# CFA_s.net
KiCad netlist of a schematic drawn in EAGLE
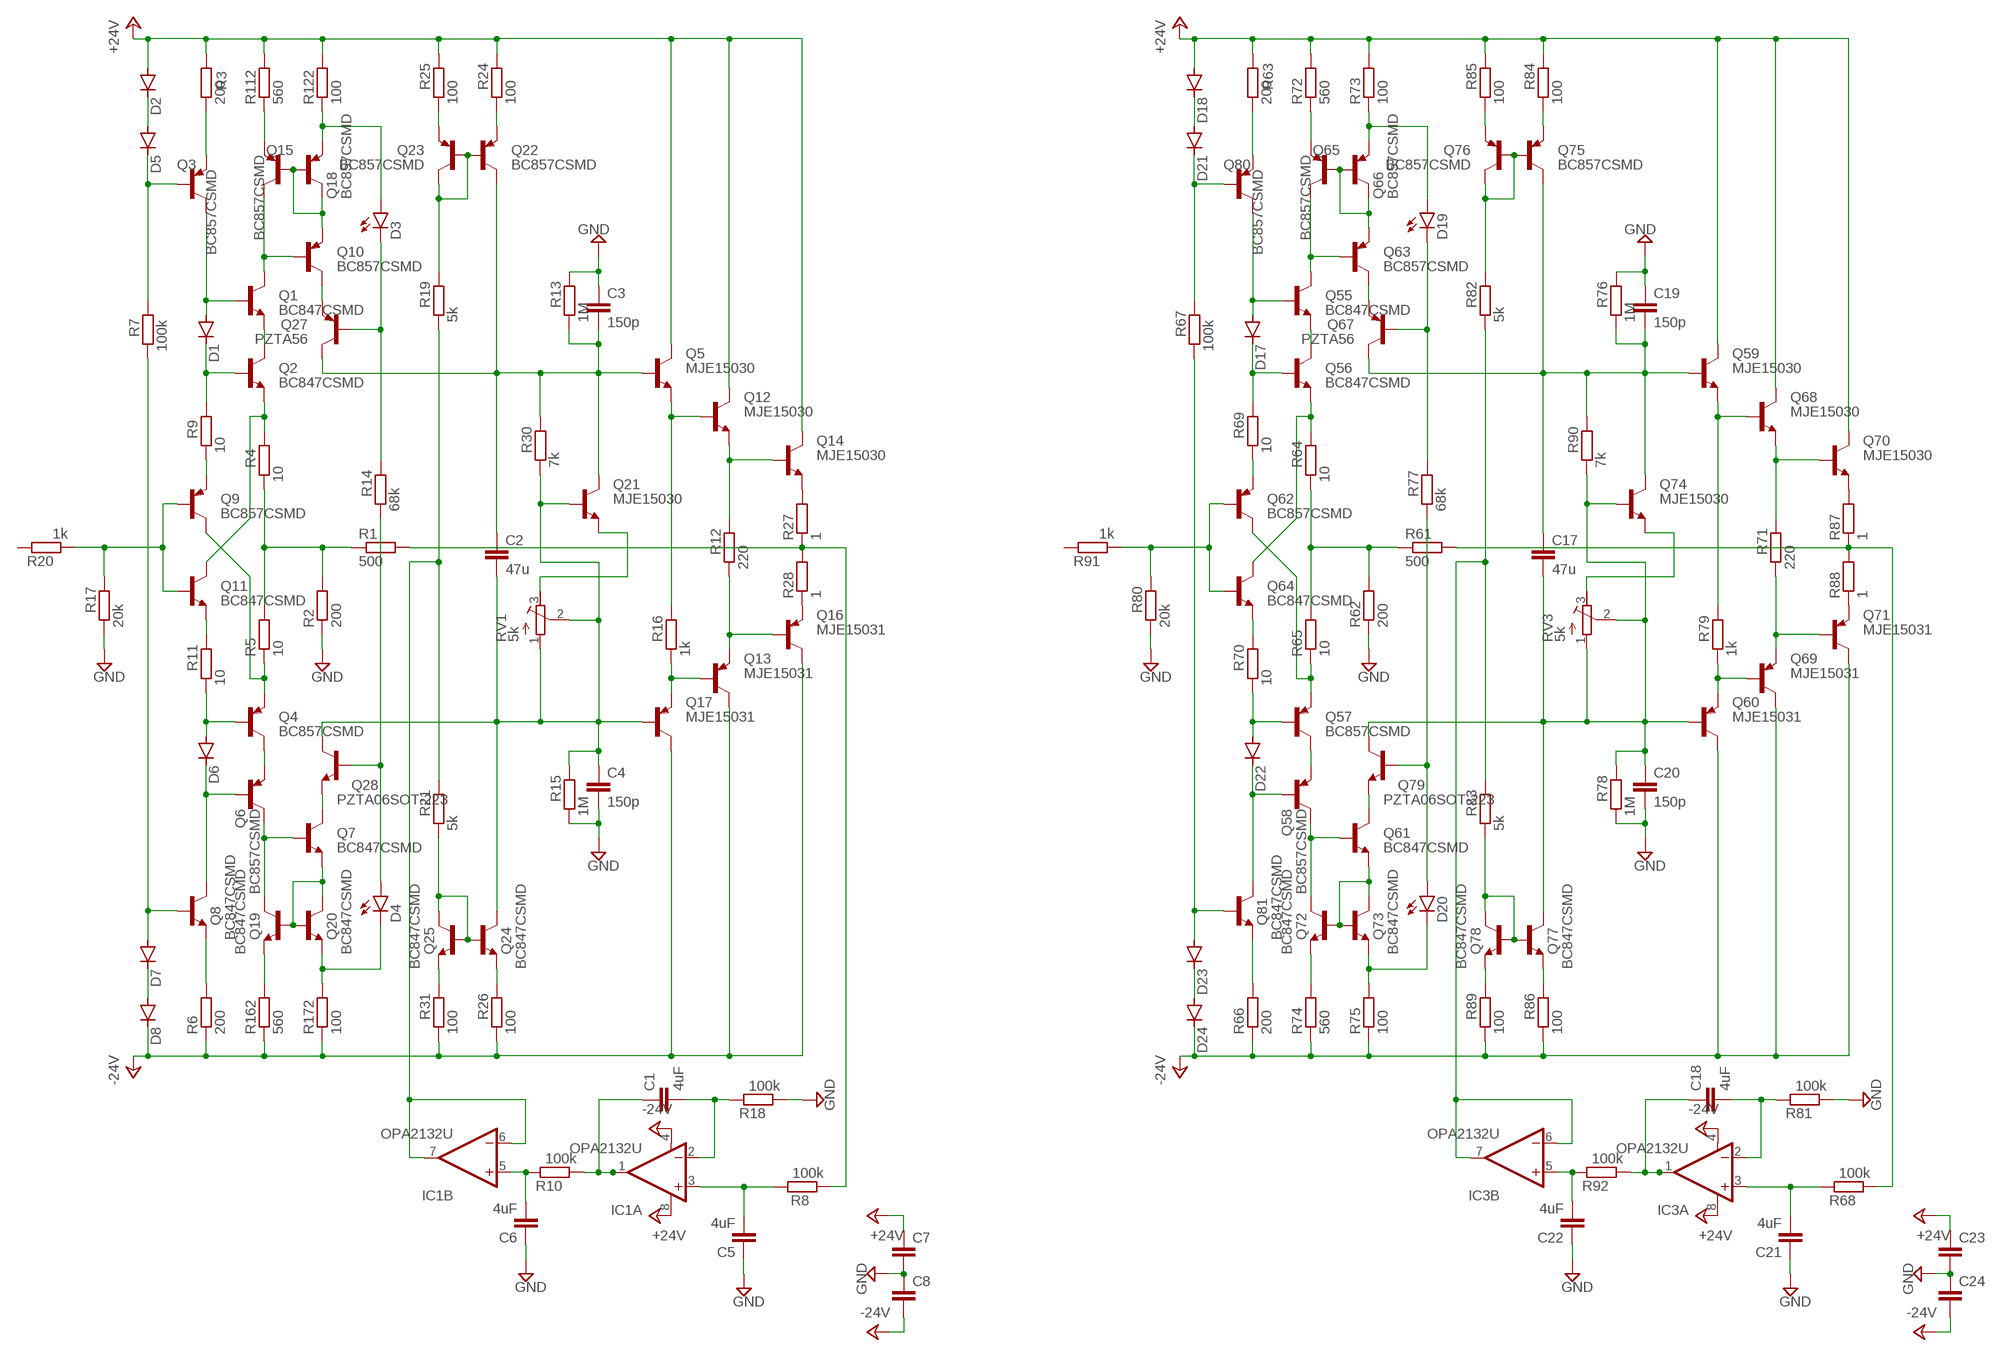
[diagram p0: schematic, sheet 1]

(export (version "E")
  (design (tool "Eeschema 10.0.6"))
  (components
    (comp (ref "C1")
      (value "4uF")
      (footprint "eagle-import:C1210")
      (fields (field (name "SPICEPREFIX") "C"))
      (libsource (lib "eagle-import") (part "C-EUC1210"))
    )
    (comp (ref "C2")
      (value "47u")
      (footprint "eagle-import:C1210")
      (fields (field (name "SPICEPREFIX") "C"))
      (libsource (lib "eagle-import") (part "C-EUC1210"))
    )
    (comp (ref "C3")
      (value "150p")
      (footprint "eagle-import:C0805")
      (fields (field (name "SPICEPREFIX") "C"))
      (libsource (lib "eagle-import") (part "C-EUC0805"))
    )
    (comp (ref "C4")
      (value "150p")
      (footprint "eagle-import:C0805")
      (fields (field (name "SPICEPREFIX") "C"))
      (libsource (lib "eagle-import") (part "C-EUC0805"))
    )
    (comp (ref "C5")
      (value "4uF")
      (footprint "eagle-import:C1210")
      (fields (field (name "SPICEPREFIX") "C"))
      (libsource (lib "eagle-import") (part "C-EUC1210"))
    )
    (comp (ref "C6")
      (value "4uF")
      (footprint "eagle-import:C1210")
      (fields (field (name "SPICEPREFIX") "C"))
      (libsource (lib "eagle-import") (part "C-EUC1210"))
    )
    (comp (ref "C7")
      (value "C-EUC0603K")
      (footprint "eagle-import:C0603K")
      (libsource (lib "eagle-import") (part "C-EUC0603K"))
    )
    (comp (ref "C8")
      (value "C-EUC0603K")
      (footprint "eagle-import:C0603K")
      (libsource (lib "eagle-import") (part "C-EUC0603K"))
    )
    (comp (ref "C17")
      (value "47u")
      (footprint "eagle-import:C1210")
      (fields (field (name "SPICEPREFIX") "C"))
      (libsource (lib "eagle-import") (part "C-EUC1210"))
    )
    (comp (ref "C18")
      (value "4uF")
      (footprint "eagle-import:C1210")
      (fields (field (name "SPICEPREFIX") "C"))
      (libsource (lib "eagle-import") (part "C-EUC1210"))
    )
    (comp (ref "C19")
      (value "150p")
      (footprint "eagle-import:C0805")
      (fields (field (name "SPICEPREFIX") "C"))
      (libsource (lib "eagle-import") (part "C-EUC0805"))
    )
    (comp (ref "C20")
      (value "150p")
      (footprint "eagle-import:C0805")
      (fields (field (name "SPICEPREFIX") "C"))
      (libsource (lib "eagle-import") (part "C-EUC0805"))
    )
    (comp (ref "C21")
      (value "4uF")
      (footprint "eagle-import:C1210")
      (fields (field (name "SPICEPREFIX") "C"))
      (libsource (lib "eagle-import") (part "C-EUC1210"))
    )
    (comp (ref "C22")
      (value "4uF")
      (footprint "eagle-import:C1210")
      (fields (field (name "SPICEPREFIX") "C"))
      (libsource (lib "eagle-import") (part "C-EUC1210"))
    )
    (comp (ref "C23")
      (value "C-EUC0603K")
      (footprint "eagle-import:C0603K")
      (libsource (lib "eagle-import") (part "C-EUC0603K"))
    )
    (comp (ref "C24")
      (value "C-EUC0603K")
      (footprint "eagle-import:C0603K")
      (libsource (lib "eagle-import") (part "C-EUC0603K"))
    )
    (comp (ref "D1")
      (value "DIODE-SOD80C")
      (footprint "eagle-import:SOD80C")
      (fields (field (name "SPICEPREFIX") "D"))
      (libsource (lib "eagle-import") (part "DIODE-SOD80C"))
    )
    (comp (ref "D2")
      (value "DIODE-SOD80C")
      (footprint "eagle-import:SOD80C")
      (fields (field (name "SPICEPREFIX") "D"))
      (libsource (lib "eagle-import") (part "DIODE-SOD80C"))
    )
    (comp (ref "D3")
      (value "LEDCHIPLED_1206")
      (footprint "eagle-import:CHIPLED_1206")
      (fields (field (name "SPICEPREFIX") "D"))
      (libsource (lib "eagle-import") (part "LEDCHIPLED_1206"))
    )
    (comp (ref "D4")
      (value "LEDCHIPLED_1206")
      (footprint "eagle-import:CHIPLED_1206")
      (fields (field (name "SPICEPREFIX") "D"))
      (libsource (lib "eagle-import") (part "LEDCHIPLED_1206"))
    )
    (comp (ref "D5")
      (value "DIODE-SOD80C")
      (footprint "eagle-import:SOD80C")
      (fields (field (name "SPICEPREFIX") "D"))
      (libsource (lib "eagle-import") (part "DIODE-SOD80C"))
    )
    (comp (ref "D6")
      (value "DIODE-SOD80C")
      (footprint "eagle-import:SOD80C")
      (fields (field (name "SPICEPREFIX") "D"))
      (libsource (lib "eagle-import") (part "DIODE-SOD80C"))
    )
    (comp (ref "D7")
      (value "DIODE-SOD80C")
      (footprint "eagle-import:SOD80C")
      (fields (field (name "SPICEPREFIX") "D"))
      (libsource (lib "eagle-import") (part "DIODE-SOD80C"))
    )
    (comp (ref "D8")
      (value "DIODE-SOD80C")
      (footprint "eagle-import:SOD80C")
      (fields (field (name "SPICEPREFIX") "D"))
      (libsource (lib "eagle-import") (part "DIODE-SOD80C"))
    )
    (comp (ref "D17")
      (value "DIODE-SOD80C")
      (footprint "eagle-import:SOD80C")
      (fields (field (name "SPICEPREFIX") "D"))
      (libsource (lib "eagle-import") (part "DIODE-SOD80C"))
    )
    (comp (ref "D18")
      (value "DIODE-SOD80C")
      (footprint "eagle-import:SOD80C")
      (fields (field (name "SPICEPREFIX") "D"))
      (libsource (lib "eagle-import") (part "DIODE-SOD80C"))
    )
    (comp (ref "D19")
      (value "LEDCHIPLED_1206")
      (footprint "eagle-import:CHIPLED_1206")
      (fields (field (name "SPICEPREFIX") "D"))
      (libsource (lib "eagle-import") (part "LEDCHIPLED_1206"))
    )
    (comp (ref "D20")
      (value "LEDCHIPLED_1206")
      (footprint "eagle-import:CHIPLED_1206")
      (fields (field (name "SPICEPREFIX") "D"))
      (libsource (lib "eagle-import") (part "LEDCHIPLED_1206"))
    )
    (comp (ref "D21")
      (value "DIODE-SOD80C")
      (footprint "eagle-import:SOD80C")
      (fields (field (name "SPICEPREFIX") "D"))
      (libsource (lib "eagle-import") (part "DIODE-SOD80C"))
    )
    (comp (ref "D22")
      (value "DIODE-SOD80C")
      (footprint "eagle-import:SOD80C")
      (fields (field (name "SPICEPREFIX") "D"))
      (libsource (lib "eagle-import") (part "DIODE-SOD80C"))
    )
    (comp (ref "D23")
      (value "DIODE-SOD80C")
      (footprint "eagle-import:SOD80C")
      (fields (field (name "SPICEPREFIX") "D"))
      (libsource (lib "eagle-import") (part "DIODE-SOD80C"))
    )
    (comp (ref "D24")
      (value "DIODE-SOD80C")
      (footprint "eagle-import:SOD80C")
      (fields (field (name "SPICEPREFIX") "D"))
      (libsource (lib "eagle-import") (part "DIODE-SOD80C"))
    )
    (comp (ref "IC1")
      (value "OPA2132U")
      (footprint "eagle-import:SO08")
      (fields (field (name "MF") "TEXAS INSTRUMENTS"))
      (libsource (lib "eagle-import") (part "OPA2132U"))
    )
    (comp (ref "IC3")
      (value "OPA2132U")
      (footprint "eagle-import:SO08")
      (fields (field (name "MF") "TEXAS INSTRUMENTS"))
      (libsource (lib "eagle-import") (part "OPA2132U"))
    )
    (comp (ref "Q1")
      (value "BC847CSMD")
      (footprint "eagle-import:SOT23")
      (fields (field (name "SPICEPREFIX") "Q"))
      (libsource (lib "eagle-import") (part "BC847SMDC"))
    )
    (comp (ref "Q2")
      (value "BC847CSMD")
      (footprint "eagle-import:SOT23")
      (fields (field (name "SPICEPREFIX") "Q"))
      (libsource (lib "eagle-import") (part "BC847SMDC"))
    )
    (comp (ref "Q3")
      (value "BC857CSMD")
      (footprint "eagle-import:SOT23-BEC")
      (fields (field (name "SPICEPREFIX") "Q"))
      (libsource (lib "eagle-import") (part "BC857SMDC"))
    )
    (comp (ref "Q4")
      (value "BC857CSMD")
      (footprint "eagle-import:SOT23-BEC")
      (fields (field (name "SPICEPREFIX") "Q"))
      (libsource (lib "eagle-import") (part "BC857SMDC"))
    )
    (comp (ref "Q5")
      (value "MJE15030")
      (footprint "eagle-import:DPAK")
      (fields (field (name "SPICEPREFIX") "Q"))
      (libsource (lib "eagle-import") (part "MJD31C"))
    )
    (comp (ref "Q6")
      (value "BC857CSMD")
      (footprint "eagle-import:SOT23-BEC")
      (fields (field (name "SPICEPREFIX") "Q"))
      (libsource (lib "eagle-import") (part "BC857SMDC"))
    )
    (comp (ref "Q7")
      (value "BC847CSMD")
      (footprint "eagle-import:SOT23")
      (fields (field (name "SPICEPREFIX") "Q"))
      (libsource (lib "eagle-import") (part "BC847SMDC"))
    )
    (comp (ref "Q8")
      (value "BC847CSMD")
      (footprint "eagle-import:SOT23")
      (fields (field (name "SPICEPREFIX") "Q"))
      (libsource (lib "eagle-import") (part "BC847SMDC"))
    )
    (comp (ref "Q9")
      (value "BC857CSMD")
      (footprint "eagle-import:SOT23-BEC")
      (fields (field (name "SPICEPREFIX") "Q"))
      (libsource (lib "eagle-import") (part "BC857SMDC"))
    )
    (comp (ref "Q10")
      (value "BC857CSMD")
      (footprint "eagle-import:SOT23-BEC")
      (fields (field (name "SPICEPREFIX") "Q"))
      (libsource (lib "eagle-import") (part "BC857SMDC"))
    )
    (comp (ref "Q11")
      (value "BC847CSMD")
      (footprint "eagle-import:SOT23")
      (fields (field (name "SPICEPREFIX") "Q"))
      (libsource (lib "eagle-import") (part "BC847SMDC"))
    )
    (comp (ref "Q12")
      (value "MJE15030")
      (footprint "eagle-import:DPAK")
      (fields (field (name "SPICEPREFIX") "Q"))
      (libsource (lib "eagle-import") (part "MJD31C"))
    )
    (comp (ref "Q13")
      (value "MJE15031")
      (footprint "eagle-import:DPAK")
      (fields (field (name "SPICEPREFIX") "Q"))
      (libsource (lib "eagle-import") (part "MJD32C"))
    )
    (comp (ref "Q14")
      (value "MJE15030")
      (footprint "eagle-import:DPAK")
      (fields (field (name "SPICEPREFIX") "Q"))
      (libsource (lib "eagle-import") (part "MJD31C"))
    )
    (comp (ref "Q15")
      (value "BC857CSMD")
      (footprint "eagle-import:SOT23-BEC")
      (fields (field (name "SPICEPREFIX") "Q"))
      (libsource (lib "eagle-import") (part "BC857SMDC"))
    )
    (comp (ref "Q16")
      (value "MJE15031")
      (footprint "eagle-import:DPAK")
      (fields (field (name "SPICEPREFIX") "Q"))
      (libsource (lib "eagle-import") (part "MJD32C"))
    )
    (comp (ref "Q17")
      (value "MJE15031")
      (footprint "eagle-import:DPAK")
      (fields (field (name "SPICEPREFIX") "Q"))
      (libsource (lib "eagle-import") (part "MJD32C"))
    )
    (comp (ref "Q18")
      (value "BC857CSMD")
      (footprint "eagle-import:SOT23-BEC")
      (fields (field (name "SPICEPREFIX") "Q"))
      (libsource (lib "eagle-import") (part "BC857SMDC"))
    )
    (comp (ref "Q19")
      (value "BC847CSMD")
      (footprint "eagle-import:SOT23")
      (fields (field (name "SPICEPREFIX") "Q"))
      (libsource (lib "eagle-import") (part "BC847SMDC"))
    )
    (comp (ref "Q20")
      (value "BC847CSMD")
      (footprint "eagle-import:SOT23")
      (fields (field (name "SPICEPREFIX") "Q"))
      (libsource (lib "eagle-import") (part "BC847SMDC"))
    )
    (comp (ref "Q21")
      (value "MJE15030")
      (footprint "eagle-import:DPAK")
      (fields (field (name "SPICEPREFIX") "Q"))
      (libsource (lib "eagle-import") (part "MJD31C"))
    )
    (comp (ref "Q22")
      (value "BC857CSMD")
      (footprint "eagle-import:SOT23-BEC")
      (fields (field (name "SPICEPREFIX") "Q"))
      (libsource (lib "eagle-import") (part "BC857SMDC"))
    )
    (comp (ref "Q23")
      (value "BC857CSMD")
      (footprint "eagle-import:SOT23-BEC")
      (fields (field (name "SPICEPREFIX") "Q"))
      (libsource (lib "eagle-import") (part "BC857SMDC"))
    )
    (comp (ref "Q24")
      (value "BC847CSMD")
      (footprint "eagle-import:SOT23")
      (fields (field (name "SPICEPREFIX") "Q"))
      (libsource (lib "eagle-import") (part "BC847SMDC"))
    )
    (comp (ref "Q25")
      (value "BC847CSMD")
      (footprint "eagle-import:SOT23")
      (fields (field (name "SPICEPREFIX") "Q"))
      (libsource (lib "eagle-import") (part "BC847SMDC"))
    )
    (comp (ref "Q27")
      (value "PZTA56")
      (footprint "eagle-import:SOT223")
      (fields (field (name "SPICEPREFIX") "Q"))
      (libsource (lib "eagle-import") (part "PZTA56"))
    )
    (comp (ref "Q28")
      (value "PZTA06SOT-223")
      (footprint "eagle-import:SOT223")
      (fields (field (name "SPICEPREFIX") "Q"))
      (libsource (lib "eagle-import") (part "PZTA06SOT-223"))
    )
    (comp (ref "Q55")
      (value "BC847CSMD")
      (footprint "eagle-import:SOT23")
      (fields (field (name "SPICEPREFIX") "Q"))
      (libsource (lib "eagle-import") (part "BC847SMDC"))
    )
    (comp (ref "Q56")
      (value "BC847CSMD")
      (footprint "eagle-import:SOT23")
      (fields (field (name "SPICEPREFIX") "Q"))
      (libsource (lib "eagle-import") (part "BC847SMDC"))
    )
    (comp (ref "Q57")
      (value "BC857CSMD")
      (footprint "eagle-import:SOT23-BEC")
      (fields (field (name "SPICEPREFIX") "Q"))
      (libsource (lib "eagle-import") (part "BC857SMDC"))
    )
    (comp (ref "Q58")
      (value "BC857CSMD")
      (footprint "eagle-import:SOT23-BEC")
      (fields (field (name "SPICEPREFIX") "Q"))
      (libsource (lib "eagle-import") (part "BC857SMDC"))
    )
    (comp (ref "Q59")
      (value "MJE15030")
      (footprint "eagle-import:DPAK")
      (fields (field (name "SPICEPREFIX") "Q"))
      (libsource (lib "eagle-import") (part "MJD31C"))
    )
    (comp (ref "Q60")
      (value "MJE15031")
      (footprint "eagle-import:DPAK")
      (fields (field (name "SPICEPREFIX") "Q"))
      (libsource (lib "eagle-import") (part "MJD32C"))
    )
    (comp (ref "Q61")
      (value "BC847CSMD")
      (footprint "eagle-import:SOT23")
      (fields (field (name "SPICEPREFIX") "Q"))
      (libsource (lib "eagle-import") (part "BC847SMDC"))
    )
    (comp (ref "Q62")
      (value "BC857CSMD")
      (footprint "eagle-import:SOT23-BEC")
      (fields (field (name "SPICEPREFIX") "Q"))
      (libsource (lib "eagle-import") (part "BC857SMDC"))
    )
    (comp (ref "Q63")
      (value "BC857CSMD")
      (footprint "eagle-import:SOT23-BEC")
      (fields (field (name "SPICEPREFIX") "Q"))
      (libsource (lib "eagle-import") (part "BC857SMDC"))
    )
    (comp (ref "Q64")
      (value "BC847CSMD")
      (footprint "eagle-import:SOT23")
      (fields (field (name "SPICEPREFIX") "Q"))
      (libsource (lib "eagle-import") (part "BC847SMDC"))
    )
    (comp (ref "Q65")
      (value "BC857CSMD")
      (footprint "eagle-import:SOT23-BEC")
      (fields (field (name "SPICEPREFIX") "Q"))
      (libsource (lib "eagle-import") (part "BC857SMDC"))
    )
    (comp (ref "Q66")
      (value "BC857CSMD")
      (footprint "eagle-import:SOT23-BEC")
      (fields (field (name "SPICEPREFIX") "Q"))
      (libsource (lib "eagle-import") (part "BC857SMDC"))
    )
    (comp (ref "Q67")
      (value "PZTA56")
      (footprint "eagle-import:SOT223")
      (fields (field (name "SPICEPREFIX") "Q"))
      (libsource (lib "eagle-import") (part "PZTA56"))
    )
    (comp (ref "Q68")
      (value "MJE15030")
      (footprint "eagle-import:DPAK")
      (fields (field (name "SPICEPREFIX") "Q"))
      (libsource (lib "eagle-import") (part "MJD31C"))
    )
    (comp (ref "Q69")
      (value "MJE15031")
      (footprint "eagle-import:DPAK")
      (fields (field (name "SPICEPREFIX") "Q"))
      (libsource (lib "eagle-import") (part "MJD32C"))
    )
    (comp (ref "Q70")
      (value "MJE15030")
      (footprint "eagle-import:DPAK")
      (fields (field (name "SPICEPREFIX") "Q"))
      (libsource (lib "eagle-import") (part "MJD31C"))
    )
    (comp (ref "Q71")
      (value "MJE15031")
      (footprint "eagle-import:DPAK")
      (fields (field (name "SPICEPREFIX") "Q"))
      (libsource (lib "eagle-import") (part "MJD32C"))
    )
    (comp (ref "Q72")
      (value "BC847CSMD")
      (footprint "eagle-import:SOT23")
      (fields (field (name "SPICEPREFIX") "Q"))
      (libsource (lib "eagle-import") (part "BC847SMDC"))
    )
    (comp (ref "Q73")
      (value "BC847CSMD")
      (footprint "eagle-import:SOT23")
      (fields (field (name "SPICEPREFIX") "Q"))
      (libsource (lib "eagle-import") (part "BC847SMDC"))
    )
    (comp (ref "Q74")
      (value "MJE15030")
      (footprint "eagle-import:DPAK")
      (fields (field (name "SPICEPREFIX") "Q"))
      (libsource (lib "eagle-import") (part "MJD31C"))
    )
    (comp (ref "Q75")
      (value "BC857CSMD")
      (footprint "eagle-import:SOT23-BEC")
      (fields (field (name "SPICEPREFIX") "Q"))
      (libsource (lib "eagle-import") (part "BC857SMDC"))
    )
    (comp (ref "Q76")
      (value "BC857CSMD")
      (footprint "eagle-import:SOT23-BEC")
      (fields (field (name "SPICEPREFIX") "Q"))
      (libsource (lib "eagle-import") (part "BC857SMDC"))
    )
    (comp (ref "Q77")
      (value "BC847CSMD")
      (footprint "eagle-import:SOT23")
      (fields (field (name "SPICEPREFIX") "Q"))
      (libsource (lib "eagle-import") (part "BC847SMDC"))
    )
    (comp (ref "Q78")
      (value "BC847CSMD")
      (footprint "eagle-import:SOT23")
      (fields (field (name "SPICEPREFIX") "Q"))
      (libsource (lib "eagle-import") (part "BC847SMDC"))
    )
    (comp (ref "Q79")
      (value "PZTA06SOT-223")
      (footprint "eagle-import:SOT223")
      (fields (field (name "SPICEPREFIX") "Q"))
      (libsource (lib "eagle-import") (part "PZTA06SOT-223"))
    )
    (comp (ref "Q80")
      (value "BC857CSMD")
      (footprint "eagle-import:SOT23-BEC")
      (fields (field (name "SPICEPREFIX") "Q"))
      (libsource (lib "eagle-import") (part "BC857SMDC"))
    )
    (comp (ref "Q81")
      (value "BC847CSMD")
      (footprint "eagle-import:SOT23")
      (fields (field (name "SPICEPREFIX") "Q"))
      (libsource (lib "eagle-import") (part "BC847SMDC"))
    )
    (comp (ref "R1")
      (value "500")
      (footprint "eagle-import:MINI_MELF-0204W")
      (fields (field (name "SPICEPREFIX") "R"))
      (libsource (lib "eagle-import") (part "R-EU_MELF0204W"))
    )
    (comp (ref "R2")
      (value "200")
      (footprint "eagle-import:MINI_MELF-0204W")
      (fields (field (name "SPICEPREFIX") "R"))
      (libsource (lib "eagle-import") (part "R-EU_MELF0204W"))
    )
    (comp (ref "R3")
      (value "200")
      (footprint "eagle-import:MINI_MELF-0204W")
      (fields (field (name "SPICEPREFIX") "R"))
      (libsource (lib "eagle-import") (part "R-EU_MELF0204W"))
    )
    (comp (ref "R4")
      (value "10")
      (footprint "eagle-import:MINI_MELF-0204W")
      (fields (field (name "SPICEPREFIX") "R"))
      (libsource (lib "eagle-import") (part "R-EU_MELF0204W"))
    )
    (comp (ref "R5")
      (value "10")
      (footprint "eagle-import:MINI_MELF-0204W")
      (fields (field (name "SPICEPREFIX") "R"))
      (libsource (lib "eagle-import") (part "R-EU_MELF0204W"))
    )
    (comp (ref "R6")
      (value "200")
      (footprint "eagle-import:MINI_MELF-0204W")
      (fields (field (name "SPICEPREFIX") "R"))
      (libsource (lib "eagle-import") (part "R-EU_MELF0204W"))
    )
    (comp (ref "R7")
      (value "100k")
      (footprint "eagle-import:MINI_MELF-0204W")
      (fields (field (name "SPICEPREFIX") "R"))
      (libsource (lib "eagle-import") (part "R-EU_MELF0204W"))
    )
    (comp (ref "R8")
      (value "100k")
      (footprint "eagle-import:MINI_MELF-0204W")
      (fields (field (name "SPICEPREFIX") "R"))
      (libsource (lib "eagle-import") (part "R-EU_MELF0204W"))
    )
    (comp (ref "R9")
      (value "10")
      (footprint "eagle-import:MINI_MELF-0204W")
      (fields (field (name "SPICEPREFIX") "R"))
      (libsource (lib "eagle-import") (part "R-EU_MELF0204W"))
    )
    (comp (ref "R10")
      (value "100k")
      (footprint "eagle-import:MINI_MELF-0204W")
      (fields (field (name "SPICEPREFIX") "R"))
      (libsource (lib "eagle-import") (part "R-EU_MELF0204W"))
    )
    (comp (ref "R11")
      (value "10")
      (footprint "eagle-import:MINI_MELF-0204W")
      (fields (field (name "SPICEPREFIX") "R"))
      (libsource (lib "eagle-import") (part "R-EU_MELF0204W"))
    )
    (comp (ref "R12")
      (value "220")
      (footprint "eagle-import:MINI_MELF-0204W")
      (fields (field (name "SPICEPREFIX") "R"))
      (libsource (lib "eagle-import") (part "R-EU_MELF0204W"))
    )
    (comp (ref "R13")
      (value "1M")
      (footprint "eagle-import:MINI_MELF-0204W")
      (fields (field (name "SPICEPREFIX") "R"))
      (libsource (lib "eagle-import") (part "R-EU_MELF0204W"))
    )
    (comp (ref "R14")
      (value "68k")
      (footprint "eagle-import:MINI_MELF-0204W")
      (fields (field (name "SPICEPREFIX") "R"))
      (libsource (lib "eagle-import") (part "R-EU_MELF0204W"))
    )
    (comp (ref "R15")
      (value "1M")
      (footprint "eagle-import:MINI_MELF-0204W")
      (fields (field (name "SPICEPREFIX") "R"))
      (libsource (lib "eagle-import") (part "R-EU_MELF0204W"))
    )
    (comp (ref "R16")
      (value "1k")
      (footprint "eagle-import:MINI_MELF-0204W")
      (fields (field (name "SPICEPREFIX") "R"))
      (libsource (lib "eagle-import") (part "R-EU_MELF0204W"))
    )
    (comp (ref "R17")
      (value "20k")
      (footprint "eagle-import:MINI_MELF-0204W")
      (fields (field (name "SPICEPREFIX") "R"))
      (libsource (lib "eagle-import") (part "R-EU_MELF0204W"))
    )
    (comp (ref "R18")
      (value "100k")
      (footprint "eagle-import:MINI_MELF-0204W")
      (fields (field (name "SPICEPREFIX") "R"))
      (libsource (lib "eagle-import") (part "R-EU_MELF0204W"))
    )
    (comp (ref "R19")
      (value "5k")
      (footprint "eagle-import:MINI_MELF-0204W")
      (fields (field (name "SPICEPREFIX") "R"))
      (libsource (lib "eagle-import") (part "R-EU_MELF0204W"))
    )
    (comp (ref "R20")
      (value "1k")
      (footprint "eagle-import:MINI_MELF-0204W")
      (fields (field (name "SPICEPREFIX") "R"))
      (libsource (lib "eagle-import") (part "R-EU_MELF0204W"))
    )
    (comp (ref "R21")
      (value "5k")
      (footprint "eagle-import:MINI_MELF-0204W")
      (fields (field (name "SPICEPREFIX") "R"))
      (libsource (lib "eagle-import") (part "R-EU_MELF0204W"))
    )
    (comp (ref "R24")
      (value "100")
      (footprint "eagle-import:MINI_MELF-0204W")
      (fields (field (name "SPICEPREFIX") "R"))
      (libsource (lib "eagle-import") (part "R-EU_MELF0204W"))
    )
    (comp (ref "R25")
      (value "100")
      (footprint "eagle-import:MINI_MELF-0204W")
      (fields (field (name "SPICEPREFIX") "R"))
      (libsource (lib "eagle-import") (part "R-EU_MELF0204W"))
    )
    (comp (ref "R26")
      (value "100")
      (footprint "eagle-import:MINI_MELF-0204W")
      (fields (field (name "SPICEPREFIX") "R"))
      (libsource (lib "eagle-import") (part "R-EU_MELF0204W"))
    )
    (comp (ref "R27")
      (value "1")
      (footprint "eagle-import:R4527")
      (fields (field (name "SPICEPREFIX") "R"))
      (libsource (lib "eagle-import") (part "R-EU_R4527"))
    )
    (comp (ref "R28")
      (value "1")
      (footprint "eagle-import:R4527")
      (fields (field (name "SPICEPREFIX") "R"))
      (libsource (lib "eagle-import") (part "R-EU_R4527"))
    )
    (comp (ref "R30")
      (value "7k")
      (footprint "eagle-import:MINI_MELF-0204W")
      (fields (field (name "SPICEPREFIX") "R"))
      (libsource (lib "eagle-import") (part "R-EU_MELF0204W"))
    )
    (comp (ref "R31")
      (value "100")
      (footprint "eagle-import:MINI_MELF-0204W")
      (fields (field (name "SPICEPREFIX") "R"))
      (libsource (lib "eagle-import") (part "R-EU_MELF0204W"))
    )
    (comp (ref "R61")
      (value "500")
      (footprint "eagle-import:MINI_MELF-0204W")
      (fields (field (name "SPICEPREFIX") "R"))
      (libsource (lib "eagle-import") (part "R-EU_MELF0204W"))
    )
    (comp (ref "R62")
      (value "200")
      (footprint "eagle-import:MINI_MELF-0204W")
      (fields (field (name "SPICEPREFIX") "R"))
      (libsource (lib "eagle-import") (part "R-EU_MELF0204W"))
    )
    (comp (ref "R63")
      (value "200")
      (footprint "eagle-import:MINI_MELF-0204W")
      (fields (field (name "SPICEPREFIX") "R"))
      (libsource (lib "eagle-import") (part "R-EU_MELF0204W"))
    )
    (comp (ref "R64")
      (value "10")
      (footprint "eagle-import:MINI_MELF-0204W")
      (fields (field (name "SPICEPREFIX") "R"))
      (libsource (lib "eagle-import") (part "R-EU_MELF0204W"))
    )
    (comp (ref "R65")
      (value "10")
      (footprint "eagle-import:MINI_MELF-0204W")
      (fields (field (name "SPICEPREFIX") "R"))
      (libsource (lib "eagle-import") (part "R-EU_MELF0204W"))
    )
    (comp (ref "R66")
      (value "200")
      (footprint "eagle-import:MINI_MELF-0204W")
      (fields (field (name "SPICEPREFIX") "R"))
      (libsource (lib "eagle-import") (part "R-EU_MELF0204W"))
    )
    (comp (ref "R67")
      (value "100k")
      (footprint "eagle-import:MINI_MELF-0204W")
      (fields (field (name "SPICEPREFIX") "R"))
      (libsource (lib "eagle-import") (part "R-EU_MELF0204W"))
    )
    (comp (ref "R68")
      (value "100k")
      (footprint "eagle-import:MINI_MELF-0204W")
      (fields (field (name "SPICEPREFIX") "R"))
      (libsource (lib "eagle-import") (part "R-EU_MELF0204W"))
    )
    (comp (ref "R69")
      (value "10")
      (footprint "eagle-import:MINI_MELF-0204W")
      (fields (field (name "SPICEPREFIX") "R"))
      (libsource (lib "eagle-import") (part "R-EU_MELF0204W"))
    )
    (comp (ref "R70")
      (value "10")
      (footprint "eagle-import:MINI_MELF-0204W")
      (fields (field (name "SPICEPREFIX") "R"))
      (libsource (lib "eagle-import") (part "R-EU_MELF0204W"))
    )
    (comp (ref "R71")
      (value "220")
      (footprint "eagle-import:MINI_MELF-0204W")
      (fields (field (name "SPICEPREFIX") "R"))
      (libsource (lib "eagle-import") (part "R-EU_MELF0204W"))
    )
    (comp (ref "R72")
      (value "560")
      (footprint "eagle-import:MINI_MELF-0204W")
      (fields (field (name "SPICEPREFIX") "R"))
      (libsource (lib "eagle-import") (part "R-EU_MELF0204W"))
    )
    (comp (ref "R73")
      (value "100")
      (footprint "eagle-import:MINI_MELF-0204W")
      (fields (field (name "SPICEPREFIX") "R"))
      (libsource (lib "eagle-import") (part "R-EU_MELF0204W"))
    )
    (comp (ref "R74")
      (value "560")
      (footprint "eagle-import:MINI_MELF-0204W")
      (fields (field (name "SPICEPREFIX") "R"))
      (libsource (lib "eagle-import") (part "R-EU_MELF0204W"))
    )
    (comp (ref "R75")
      (value "100")
      (footprint "eagle-import:MINI_MELF-0204W")
      (fields (field (name "SPICEPREFIX") "R"))
      (libsource (lib "eagle-import") (part "R-EU_MELF0204W"))
    )
    (comp (ref "R76")
      (value "1M")
      (footprint "eagle-import:MINI_MELF-0204W")
      (fields (field (name "SPICEPREFIX") "R"))
      (libsource (lib "eagle-import") (part "R-EU_MELF0204W"))
    )
    (comp (ref "R77")
      (value "68k")
      (footprint "eagle-import:MINI_MELF-0204W")
      (fields (field (name "SPICEPREFIX") "R"))
      (libsource (lib "eagle-import") (part "R-EU_MELF0204W"))
    )
    (comp (ref "R78")
      (value "1M")
      (footprint "eagle-import:MINI_MELF-0204W")
      (fields (field (name "SPICEPREFIX") "R"))
      (libsource (lib "eagle-import") (part "R-EU_MELF0204W"))
    )
    (comp (ref "R79")
      (value "1k")
      (footprint "eagle-import:MINI_MELF-0204W")
      (fields (field (name "SPICEPREFIX") "R"))
      (libsource (lib "eagle-import") (part "R-EU_MELF0204W"))
    )
    (comp (ref "R80")
      (value "20k")
      (footprint "eagle-import:MINI_MELF-0204W")
      (fields (field (name "SPICEPREFIX") "R"))
      (libsource (lib "eagle-import") (part "R-EU_MELF0204W"))
    )
    (comp (ref "R81")
      (value "100k")
      (footprint "eagle-import:MINI_MELF-0204W")
      (fields (field (name "SPICEPREFIX") "R"))
      (libsource (lib "eagle-import") (part "R-EU_MELF0204W"))
    )
    (comp (ref "R82")
      (value "5k")
      (footprint "eagle-import:MINI_MELF-0204W")
      (fields (field (name "SPICEPREFIX") "R"))
      (libsource (lib "eagle-import") (part "R-EU_MELF0204W"))
    )
    (comp (ref "R83")
      (value "5k")
      (footprint "eagle-import:MINI_MELF-0204W")
      (fields (field (name "SPICEPREFIX") "R"))
      (libsource (lib "eagle-import") (part "R-EU_MELF0204W"))
    )
    (comp (ref "R84")
      (value "100")
      (footprint "eagle-import:MINI_MELF-0204W")
      (fields (field (name "SPICEPREFIX") "R"))
      (libsource (lib "eagle-import") (part "R-EU_MELF0204W"))
    )
    (comp (ref "R85")
      (value "100")
      (footprint "eagle-import:MINI_MELF-0204W")
      (fields (field (name "SPICEPREFIX") "R"))
      (libsource (lib "eagle-import") (part "R-EU_MELF0204W"))
    )
    (comp (ref "R86")
      (value "100")
      (footprint "eagle-import:MINI_MELF-0204W")
      (fields (field (name "SPICEPREFIX") "R"))
      (libsource (lib "eagle-import") (part "R-EU_MELF0204W"))
    )
    (comp (ref "R87")
      (value "1")
      (footprint "eagle-import:R4527")
      (fields (field (name "SPICEPREFIX") "R"))
      (libsource (lib "eagle-import") (part "R-EU_R4527"))
    )
    (comp (ref "R88")
      (value "1")
      (footprint "eagle-import:R4527")
      (fields (field (name "SPICEPREFIX") "R"))
      (libsource (lib "eagle-import") (part "R-EU_R4527"))
    )
    (comp (ref "R89")
      (value "100")
      (footprint "eagle-import:MINI_MELF-0204W")
      (fields (field (name "SPICEPREFIX") "R"))
      (libsource (lib "eagle-import") (part "R-EU_MELF0204W"))
    )
    (comp (ref "R90")
      (value "7k")
      (footprint "eagle-import:MINI_MELF-0204W")
      (fields (field (name "SPICEPREFIX") "R"))
      (libsource (lib "eagle-import") (part "R-EU_MELF0204W"))
    )
    (comp (ref "R91")
      (value "1k")
      (footprint "eagle-import:MINI_MELF-0204W")
      (fields (field (name "SPICEPREFIX") "R"))
      (libsource (lib "eagle-import") (part "R-EU_MELF0204W"))
    )
    (comp (ref "R92")
      (value "100k")
      (footprint "eagle-import:MINI_MELF-0204W")
      (fields (field (name "SPICEPREFIX") "R"))
      (libsource (lib "eagle-import") (part "R-EU_MELF0204W"))
    )
    (comp (ref "R112")
      (value "560")
      (footprint "eagle-import:MINI_MELF-0204W")
      (fields (field (name "SPICEPREFIX") "R"))
      (libsource (lib "eagle-import") (part "R-EU_MELF0204W"))
    )
    (comp (ref "R122")
      (value "100")
      (footprint "eagle-import:MINI_MELF-0204W")
      (fields (field (name "SPICEPREFIX") "R"))
      (libsource (lib "eagle-import") (part "R-EU_MELF0204W"))
    )
    (comp (ref "R162")
      (value "560")
      (footprint "eagle-import:MINI_MELF-0204W")
      (fields (field (name "SPICEPREFIX") "R"))
      (libsource (lib "eagle-import") (part "R-EU_MELF0204W"))
    )
    (comp (ref "R172")
      (value "100")
      (footprint "eagle-import:MINI_MELF-0204W")
      (fields (field (name "SPICEPREFIX") "R"))
      (libsource (lib "eagle-import") (part "R-EU_MELF0204W"))
    )
    (comp (ref "RV1")
      (value "5k")
      (footprint "eagle-import:RTRIMTS63Y")
      (fields (field (name "SPICEPREFIX") "Z"))
      (libsource (lib "eagle-import") (part "R-TRIMMTS63Y"))
    )
    (comp (ref "RV3")
      (value "5k")
      (footprint "eagle-import:RTRIMTS63Y")
      (fields (field (name "SPICEPREFIX") "Z"))
      (libsource (lib "eagle-import") (part "R-TRIMMTS63Y"))
    )
  )
  (nets
    (net (code "1") (name "+24V") (class "Default")
      (node (ref "C23") (pin "1") (pinfunction "1_1") (pintype "passive"))
      (node (ref "C7") (pin "1") (pinfunction "1_1") (pintype "passive"))
      (node (ref "D18") (pin "A") (pinfunction "A_A") (pintype "passive"))
      (node (ref "D2") (pin "A") (pinfunction "A_A") (pintype "passive"))
      (node (ref "IC1") (pin "8") (pinfunction "V+_8") (pintype "power_in"))
      (node (ref "IC3") (pin "8") (pinfunction "V+_8") (pintype "power_in"))
      (node (ref "Q12") (pin "4") (pinfunction "C_4") (pintype "passive"))
      (node (ref "Q14") (pin "4") (pinfunction "C_4") (pintype "passive"))
      (node (ref "Q5") (pin "4") (pinfunction "C_4") (pintype "passive"))
      (node (ref "Q59") (pin "4") (pinfunction "C_4") (pintype "passive"))
      (node (ref "Q68") (pin "4") (pinfunction "C_4") (pintype "passive"))
      (node (ref "Q70") (pin "4") (pinfunction "C_4") (pintype "passive"))
      (node (ref "R112") (pin "2") (pinfunction "2_2") (pintype "passive"))
      (node (ref "R122") (pin "2") (pinfunction "2_2") (pintype "passive"))
      (node (ref "R24") (pin "2") (pinfunction "2_2") (pintype "passive"))
      (node (ref "R25") (pin "2") (pinfunction "2_2") (pintype "passive"))
      (node (ref "R3") (pin "2") (pinfunction "2_2") (pintype "passive"))
      (node (ref "R63") (pin "2") (pinfunction "2_2") (pintype "passive"))
      (node (ref "R72") (pin "2") (pinfunction "2_2") (pintype "passive"))
      (node (ref "R73") (pin "2") (pinfunction "2_2") (pintype "passive"))
      (node (ref "R84") (pin "2") (pinfunction "2_2") (pintype "passive"))
      (node (ref "R85") (pin "2") (pinfunction "2_2") (pintype "passive"))
    )
    (net (code "2") (name "-24V") (class "Default")
      (node (ref "C24") (pin "2") (pinfunction "2_2") (pintype "passive"))
      (node (ref "C8") (pin "2") (pinfunction "2_2") (pintype "passive"))
      (node (ref "D24") (pin "C") (pinfunction "C_C") (pintype "passive"))
      (node (ref "D8") (pin "C") (pinfunction "C_C") (pintype "passive"))
      (node (ref "IC1") (pin "4") (pinfunction "V-_4") (pintype "power_in"))
      (node (ref "IC3") (pin "4") (pinfunction "V-_4") (pintype "power_in"))
      (node (ref "Q13") (pin "4") (pinfunction "C_4") (pintype "passive"))
      (node (ref "Q16") (pin "4") (pinfunction "C_4") (pintype "passive"))
      (node (ref "Q17") (pin "4") (pinfunction "C_4") (pintype "passive"))
      (node (ref "Q60") (pin "4") (pinfunction "C_4") (pintype "passive"))
      (node (ref "Q69") (pin "4") (pinfunction "C_4") (pintype "passive"))
      (node (ref "Q71") (pin "4") (pinfunction "C_4") (pintype "passive"))
      (node (ref "R162") (pin "1") (pinfunction "1_1") (pintype "passive"))
      (node (ref "R172") (pin "1") (pinfunction "1_1") (pintype "passive"))
      (node (ref "R26") (pin "1") (pinfunction "1_1") (pintype "passive"))
      (node (ref "R31") (pin "1") (pinfunction "1_1") (pintype "passive"))
      (node (ref "R6") (pin "1") (pinfunction "1_1") (pintype "passive"))
      (node (ref "R66") (pin "1") (pinfunction "1_1") (pintype "passive"))
      (node (ref "R74") (pin "1") (pinfunction "1_1") (pintype "passive"))
      (node (ref "R75") (pin "1") (pinfunction "1_1") (pintype "passive"))
      (node (ref "R86") (pin "1") (pinfunction "1_1") (pintype "passive"))
      (node (ref "R89") (pin "1") (pinfunction "1_1") (pintype "passive"))
    )
    (net (code "3") (name "GND") (class "Default")
      (node (ref "C19") (pin "1") (pinfunction "1_1") (pintype "passive"))
      (node (ref "C20") (pin "2") (pinfunction "2_2") (pintype "passive"))
      (node (ref "C21") (pin "1") (pinfunction "1_1") (pintype "passive"))
      (node (ref "C22") (pin "1") (pinfunction "1_1") (pintype "passive"))
      (node (ref "C23") (pin "2") (pinfunction "2_2") (pintype "passive"))
      (node (ref "C24") (pin "1") (pinfunction "1_1") (pintype "passive"))
      (node (ref "C3") (pin "1") (pinfunction "1_1") (pintype "passive"))
      (node (ref "C4") (pin "2") (pinfunction "2_2") (pintype "passive"))
      (node (ref "C5") (pin "1") (pinfunction "1_1") (pintype "passive"))
      (node (ref "C6") (pin "1") (pinfunction "1_1") (pintype "passive"))
      (node (ref "C7") (pin "2") (pinfunction "2_2") (pintype "passive"))
      (node (ref "C8") (pin "1") (pinfunction "1_1") (pintype "passive"))
      (node (ref "R13") (pin "2") (pinfunction "2_2") (pintype "passive"))
      (node (ref "R15") (pin "1") (pinfunction "1_1") (pintype "passive"))
      (node (ref "R17") (pin "1") (pinfunction "1_1") (pintype "passive"))
      (node (ref "R18") (pin "1") (pinfunction "1_1") (pintype "passive"))
      (node (ref "R2") (pin "1") (pinfunction "1_1") (pintype "passive"))
      (node (ref "R62") (pin "1") (pinfunction "1_1") (pintype "passive"))
      (node (ref "R76") (pin "2") (pinfunction "2_2") (pintype "passive"))
      (node (ref "R78") (pin "1") (pinfunction "1_1") (pintype "passive"))
      (node (ref "R80") (pin "1") (pinfunction "1_1") (pintype "passive"))
      (node (ref "R81") (pin "1") (pinfunction "1_1") (pintype "passive"))
    )
    (net (code "4") (name "Net-(D2-PadC)") (class "Default")
      (node (ref "D2") (pin "C") (pinfunction "C_C") (pintype "passive"))
      (node (ref "D5") (pin "A") (pinfunction "A_A") (pintype "passive"))
    )
    (net (code "5") (name "Net-(D3-PadA)") (class "Default")
      (node (ref "D3") (pin "A") (pinfunction "A_A") (pintype "passive"))
      (node (ref "Q18") (pin "E") (pinfunction "E_E") (pintype "passive"))
      (node (ref "R122") (pin "1") (pinfunction "1_1") (pintype "passive"))
    )
    (net (code "6") (name "Net-(D5-PadC)") (class "Default")
      (node (ref "D5") (pin "C") (pinfunction "C_C") (pintype "passive"))
      (node (ref "Q3") (pin "B") (pinfunction "B_B") (pintype "passive"))
      (node (ref "R7") (pin "2") (pinfunction "2_2") (pintype "passive"))
    )
    (net (code "7") (name "Net-(D6-PadA)") (class "Default")
      (node (ref "D6") (pin "A") (pinfunction "A_A") (pintype "passive"))
      (node (ref "Q4") (pin "B") (pinfunction "B_B") (pintype "passive"))
      (node (ref "R11") (pin "1") (pinfunction "1_1") (pintype "passive"))
    )
    (net (code "8") (name "Net-(D7-PadC)") (class "Default")
      (node (ref "D7") (pin "C") (pinfunction "C_C") (pintype "passive"))
      (node (ref "D8") (pin "A") (pinfunction "A_A") (pintype "passive"))
    )
    (net (code "9") (name "Net-(D18-PadC)") (class "Default")
      (node (ref "D18") (pin "C") (pinfunction "C_C") (pintype "passive"))
      (node (ref "D21") (pin "A") (pinfunction "A_A") (pintype "passive"))
    )
    (net (code "10") (name "Net-(D19-PadA)") (class "Default")
      (node (ref "D19") (pin "A") (pinfunction "A_A") (pintype "passive"))
      (node (ref "Q66") (pin "E") (pinfunction "E_E") (pintype "passive"))
      (node (ref "R73") (pin "1") (pinfunction "1_1") (pintype "passive"))
    )
    (net (code "11") (name "Net-(D21-PadC)") (class "Default")
      (node (ref "D21") (pin "C") (pinfunction "C_C") (pintype "passive"))
      (node (ref "Q80") (pin "B") (pinfunction "B_B") (pintype "passive"))
      (node (ref "R67") (pin "2") (pinfunction "2_2") (pintype "passive"))
    )
    (net (code "12") (name "Net-(D22-PadA)") (class "Default")
      (node (ref "D22") (pin "A") (pinfunction "A_A") (pintype "passive"))
      (node (ref "Q57") (pin "B") (pinfunction "B_B") (pintype "passive"))
      (node (ref "R70") (pin "1") (pinfunction "1_1") (pintype "passive"))
    )
    (net (code "13") (name "Net-(D23-PadC)") (class "Default")
      (node (ref "D23") (pin "C") (pinfunction "C_C") (pintype "passive"))
      (node (ref "D24") (pin "A") (pinfunction "A_A") (pintype "passive"))
    )
    (net (code "14") (name "Net-(IC1A-+IN)") (class "Default")
      (node (ref "C5") (pin "2") (pinfunction "2_2") (pintype "passive"))
      (node (ref "IC1") (pin "3") (pinfunction "+IN_3") (pintype "input"))
      (node (ref "R8") (pin "2") (pinfunction "2_2") (pintype "passive"))
    )
    (net (code "15") (name "Net-(IC1A--IN)") (class "Default")
      (node (ref "C1") (pin "2") (pinfunction "2_2") (pintype "passive"))
      (node (ref "IC1") (pin "2") (pinfunction "-IN_2") (pintype "input"))
      (node (ref "R18") (pin "2") (pinfunction "2_2") (pintype "passive"))
    )
    (net (code "16") (name "Net-(IC1A-OUT)") (class "Default")
      (node (ref "C1") (pin "1") (pinfunction "1_1") (pintype "passive"))
      (node (ref "IC1") (pin "1") (pinfunction "OUT_1") (pintype "output"))
      (node (ref "R10") (pin "1") (pinfunction "1_1") (pintype "passive"))
    )
    (net (code "17") (name "Net-(IC1B-+IN)") (class "Default")
      (node (ref "C6") (pin "2") (pinfunction "2_2") (pintype "passive"))
      (node (ref "IC1") (pin "5") (pinfunction "+IN_5") (pintype "input"))
      (node (ref "R10") (pin "2") (pinfunction "2_2") (pintype "passive"))
    )
    (net (code "18") (name "Net-(IC1B--IN)") (class "Default")
      (node (ref "IC1") (pin "6") (pinfunction "-IN_6") (pintype "input"))
      (node (ref "IC1") (pin "7") (pinfunction "OUT_7") (pintype "output"))
      (node (ref "R19") (pin "1") (pinfunction "1_1") (pintype "passive"))
      (node (ref "R21") (pin "2") (pinfunction "2_2") (pintype "passive"))
    )
    (net (code "19") (name "Net-(IC3A-+IN)") (class "Default")
      (node (ref "C21") (pin "2") (pinfunction "2_2") (pintype "passive"))
      (node (ref "IC3") (pin "3") (pinfunction "+IN_3") (pintype "input"))
      (node (ref "R68") (pin "2") (pinfunction "2_2") (pintype "passive"))
    )
    (net (code "20") (name "Net-(IC3A--IN)") (class "Default")
      (node (ref "C18") (pin "2") (pinfunction "2_2") (pintype "passive"))
      (node (ref "IC3") (pin "2") (pinfunction "-IN_2") (pintype "input"))
      (node (ref "R81") (pin "2") (pinfunction "2_2") (pintype "passive"))
    )
    (net (code "21") (name "Net-(IC3A-OUT)") (class "Default")
      (node (ref "C18") (pin "1") (pinfunction "1_1") (pintype "passive"))
      (node (ref "IC3") (pin "1") (pinfunction "OUT_1") (pintype "output"))
      (node (ref "R92") (pin "1") (pinfunction "1_1") (pintype "passive"))
    )
    (net (code "22") (name "Net-(IC3B-+IN)") (class "Default")
      (node (ref "C22") (pin "2") (pinfunction "2_2") (pintype "passive"))
      (node (ref "IC3") (pin "5") (pinfunction "+IN_5") (pintype "input"))
      (node (ref "R92") (pin "2") (pinfunction "2_2") (pintype "passive"))
    )
    (net (code "23") (name "Net-(IC3B--IN)") (class "Default")
      (node (ref "IC3") (pin "6") (pinfunction "-IN_6") (pintype "input"))
      (node (ref "IC3") (pin "7") (pinfunction "OUT_7") (pintype "output"))
      (node (ref "R82") (pin "1") (pinfunction "1_1") (pintype "passive"))
      (node (ref "R83") (pin "2") (pinfunction "2_2") (pintype "passive"))
    )
    (net (code "24") (name "Net-(Q1-B)") (class "Default")
      (node (ref "D1") (pin "A") (pinfunction "A_A") (pintype "passive"))
      (node (ref "Q1") (pin "1") (pinfunction "B_1") (pintype "passive"))
      (node (ref "Q3") (pin "C") (pinfunction "C_C") (pintype "passive"))
    )
    (net (code "25") (name "Net-(Q1-C)") (class "Default")
      (node (ref "Q1") (pin "3") (pinfunction "C_3") (pintype "passive"))
      (node (ref "Q10") (pin "B") (pinfunction "B_B") (pintype "passive"))
      (node (ref "Q15") (pin "C") (pinfunction "C_C") (pintype "passive"))
    )
    (net (code "26") (name "Net-(Q1-E)") (class "Default")
      (node (ref "Q1") (pin "2") (pinfunction "E_2") (pintype "passive"))
      (node (ref "Q2") (pin "3") (pinfunction "C_3") (pintype "passive"))
    )
    (net (code "27") (name "Net-(Q2-B)") (class "Default")
      (node (ref "D1") (pin "C") (pinfunction "C_C") (pintype "passive"))
      (node (ref "Q2") (pin "1") (pinfunction "B_1") (pintype "passive"))
      (node (ref "R9") (pin "2") (pinfunction "2_2") (pintype "passive"))
    )
    (net (code "28") (name "Net-(Q3-PadE)") (class "Default")
      (node (ref "Q3") (pin "E") (pinfunction "E_E") (pintype "passive"))
      (node (ref "R3") (pin "1") (pinfunction "1_1") (pintype "passive"))
    )
    (net (code "29") (name "Net-(Q4-PadC)") (class "Default")
      (node (ref "Q4") (pin "C") (pinfunction "C_C") (pintype "passive"))
      (node (ref "Q6") (pin "E") (pinfunction "E_E") (pintype "passive"))
    )
    (net (code "30") (name "Net-(Q4-PadE)") (class "Default")
      (node (ref "Q4") (pin "E") (pinfunction "E_E") (pintype "passive"))
      (node (ref "Q9") (pin "C") (pinfunction "C_C") (pintype "passive"))
      (node (ref "R5") (pin "1") (pinfunction "1_1") (pintype "passive"))
    )
    (net (code "31") (name "Net-(Q8-B)") (class "Default")
      (node (ref "D7") (pin "A") (pinfunction "A_A") (pintype "passive"))
      (node (ref "Q8") (pin "1") (pinfunction "B_1") (pintype "passive"))
      (node (ref "R7") (pin "1") (pinfunction "1_1") (pintype "passive"))
    )
    (net (code "32") (name "Net-(Q8-C)") (class "Default")
      (node (ref "D6") (pin "C") (pinfunction "C_C") (pintype "passive"))
      (node (ref "Q6") (pin "B") (pinfunction "B_B") (pintype "passive"))
      (node (ref "Q8") (pin "3") (pinfunction "C_3") (pintype "passive"))
    )
    (net (code "33") (name "Net-(Q8-E)") (class "Default")
      (node (ref "Q8") (pin "2") (pinfunction "E_2") (pintype "passive"))
      (node (ref "R6") (pin "2") (pinfunction "2_2") (pintype "passive"))
    )
    (net (code "34") (name "Net-(Q9-PadE)") (class "Default")
      (node (ref "Q9") (pin "E") (pinfunction "E_E") (pintype "passive"))
      (node (ref "R9") (pin "1") (pinfunction "1_1") (pintype "passive"))
    )
    (net (code "35") (name "Net-(Q10-PadE)") (class "Default")
      (node (ref "Q10") (pin "E") (pinfunction "E_E") (pintype "passive"))
      (node (ref "Q15") (pin "B") (pinfunction "B_B") (pintype "passive"))
      (node (ref "Q18") (pin "B") (pinfunction "B_B") (pintype "passive"))
      (node (ref "Q18") (pin "C") (pinfunction "C_C") (pintype "passive"))
    )
    (net (code "36") (name "Net-(Q11-B)") (class "Default")
      (node (ref "Q11") (pin "1") (pinfunction "B_1") (pintype "passive"))
      (node (ref "Q9") (pin "B") (pinfunction "B_B") (pintype "passive"))
      (node (ref "R17") (pin "2") (pinfunction "2_2") (pintype "passive"))
      (node (ref "R20") (pin "1") (pinfunction "1_1") (pintype "passive"))
    )
    (net (code "37") (name "Net-(Q11-C)") (class "Default")
      (node (ref "Q11") (pin "3") (pinfunction "C_3") (pintype "passive"))
      (node (ref "Q2") (pin "2") (pinfunction "E_2") (pintype "passive"))
      (node (ref "R4") (pin "2") (pinfunction "2_2") (pintype "passive"))
    )
    (net (code "38") (name "Net-(Q11-E)") (class "Default")
      (node (ref "Q11") (pin "2") (pinfunction "E_2") (pintype "passive"))
      (node (ref "R11") (pin "2") (pinfunction "2_2") (pintype "passive"))
    )
    (net (code "39") (name "Net-(Q12-B)") (class "Default")
      (node (ref "Q12") (pin "1") (pinfunction "B_1") (pintype "passive"))
      (node (ref "Q5") (pin "3") (pinfunction "E_3") (pintype "passive"))
      (node (ref "R16") (pin "2") (pinfunction "2_2") (pintype "passive"))
    )
    (net (code "40") (name "Net-(Q12-E)") (class "Default")
      (node (ref "Q12") (pin "3") (pinfunction "E_3") (pintype "passive"))
      (node (ref "Q14") (pin "1") (pinfunction "B_1") (pintype "passive"))
      (node (ref "R12") (pin "2") (pinfunction "2_2") (pintype "passive"))
    )
    (net (code "41") (name "Net-(Q13-B)") (class "Default")
      (node (ref "Q13") (pin "1") (pinfunction "B_1") (pintype "passive"))
      (node (ref "Q17") (pin "3") (pinfunction "E_3") (pintype "passive"))
      (node (ref "R16") (pin "1") (pinfunction "1_1") (pintype "passive"))
    )
    (net (code "42") (name "Net-(Q13-E)") (class "Default")
      (node (ref "Q13") (pin "3") (pinfunction "E_3") (pintype "passive"))
      (node (ref "Q16") (pin "1") (pinfunction "B_1") (pintype "passive"))
      (node (ref "R12") (pin "1") (pinfunction "1_1") (pintype "passive"))
    )
    (net (code "43") (name "Net-(Q14-E)") (class "Default")
      (node (ref "Q14") (pin "3") (pinfunction "E_3") (pintype "passive"))
      (node (ref "R27") (pin "2") (pinfunction "2_2") (pintype "passive"))
    )
    (net (code "44") (name "Net-(Q15-PadE)") (class "Default")
      (node (ref "Q15") (pin "E") (pinfunction "E_E") (pintype "passive"))
      (node (ref "R112") (pin "1") (pinfunction "1_1") (pintype "passive"))
    )
    (net (code "45") (name "Net-(Q16-E)") (class "Default")
      (node (ref "Q16") (pin "3") (pinfunction "E_3") (pintype "passive"))
      (node (ref "R28") (pin "1") (pinfunction "1_1") (pintype "passive"))
    )
    (net (code "46") (name "Net-(Q17-B)") (class "Default")
      (node (ref "C2") (pin "2") (pinfunction "2_2") (pintype "passive"))
      (node (ref "C4") (pin "1") (pinfunction "1_1") (pintype "passive"))
      (node (ref "Q17") (pin "1") (pinfunction "B_1") (pintype "passive"))
      (node (ref "Q21") (pin "1") (pinfunction "B_1") (pintype "passive"))
      (node (ref "Q24") (pin "3") (pinfunction "C_3") (pintype "passive"))
      (node (ref "Q28") (pin "2") (pinfunction "C_2") (pintype "passive"))
      (node (ref "Q28") (pin "4") (pinfunction "C_4") (pintype "passive"))
      (node (ref "R15") (pin "2") (pinfunction "2_2") (pintype "passive"))
      (node (ref "R30") (pin "1") (pinfunction "1_1") (pintype "passive"))
      (node (ref "RV1") (pin "1") (pinfunction "A_1") (pintype "passive"))
      (node (ref "RV1") (pin "2") (pinfunction "S_2") (pintype "passive"))
    )
    (net (code "47") (name "Net-(Q19-B)") (class "Default")
      (node (ref "Q19") (pin "1") (pinfunction "B_1") (pintype "passive"))
      (node (ref "Q20") (pin "1") (pinfunction "B_1") (pintype "passive"))
      (node (ref "Q20") (pin "3") (pinfunction "C_3") (pintype "passive"))
      (node (ref "Q7") (pin "2") (pinfunction "E_2") (pintype "passive"))
    )
    (net (code "48") (name "Net-(Q19-C)") (class "Default")
      (node (ref "Q19") (pin "3") (pinfunction "C_3") (pintype "passive"))
      (node (ref "Q6") (pin "C") (pinfunction "C_C") (pintype "passive"))
      (node (ref "Q7") (pin "1") (pinfunction "B_1") (pintype "passive"))
    )
    (net (code "49") (name "Net-(Q19-E)") (class "Default")
      (node (ref "Q19") (pin "2") (pinfunction "E_2") (pintype "passive"))
      (node (ref "R162") (pin "2") (pinfunction "2_2") (pintype "passive"))
    )
    (net (code "50") (name "Net-(Q20-E)") (class "Default")
      (node (ref "D4") (pin "C") (pinfunction "C_C") (pintype "passive"))
      (node (ref "Q20") (pin "2") (pinfunction "E_2") (pintype "passive"))
      (node (ref "R172") (pin "2") (pinfunction "2_2") (pintype "passive"))
    )
    (net (code "51") (name "Net-(Q21-C)") (class "Default")
      (node (ref "C2") (pin "1") (pinfunction "1_1") (pintype "passive"))
      (node (ref "C3") (pin "2") (pinfunction "2_2") (pintype "passive"))
      (node (ref "Q21") (pin "4") (pinfunction "C_4") (pintype "passive"))
      (node (ref "Q22") (pin "C") (pinfunction "C_C") (pintype "passive"))
      (node (ref "Q27") (pin "2") (pinfunction "C_2") (pintype "passive"))
      (node (ref "Q27") (pin "4") (pinfunction "C_4") (pintype "passive"))
      (node (ref "Q5") (pin "1") (pinfunction "B_1") (pintype "passive"))
      (node (ref "R13") (pin "1") (pinfunction "1_1") (pintype "passive"))
      (node (ref "R30") (pin "2") (pinfunction "2_2") (pintype "passive"))
    )
    (net (code "52") (name "Net-(Q21-E)") (class "Default")
      (node (ref "Q21") (pin "3") (pinfunction "E_3") (pintype "passive"))
      (node (ref "RV1") (pin "3") (pinfunction "E_3") (pintype "passive"))
    )
    (net (code "53") (name "Net-(Q22-PadB)") (class "Default")
      (node (ref "Q22") (pin "B") (pinfunction "B_B") (pintype "passive"))
      (node (ref "Q23") (pin "B") (pinfunction "B_B") (pintype "passive"))
      (node (ref "Q23") (pin "C") (pinfunction "C_C") (pintype "passive"))
      (node (ref "R19") (pin "2") (pinfunction "2_2") (pintype "passive"))
    )
    (net (code "54") (name "Net-(Q22-PadE)") (class "Default")
      (node (ref "Q22") (pin "E") (pinfunction "E_E") (pintype "passive"))
      (node (ref "R24") (pin "1") (pinfunction "1_1") (pintype "passive"))
    )
    (net (code "55") (name "Net-(Q23-PadE)") (class "Default")
      (node (ref "Q23") (pin "E") (pinfunction "E_E") (pintype "passive"))
      (node (ref "R25") (pin "1") (pinfunction "1_1") (pintype "passive"))
    )
    (net (code "56") (name "Net-(Q24-B)") (class "Default")
      (node (ref "Q24") (pin "1") (pinfunction "B_1") (pintype "passive"))
      (node (ref "Q25") (pin "1") (pinfunction "B_1") (pintype "passive"))
      (node (ref "Q25") (pin "3") (pinfunction "C_3") (pintype "passive"))
      (node (ref "R21") (pin "1") (pinfunction "1_1") (pintype "passive"))
    )
    (net (code "57") (name "Net-(Q24-E)") (class "Default")
      (node (ref "Q24") (pin "2") (pinfunction "E_2") (pintype "passive"))
      (node (ref "R26") (pin "2") (pinfunction "2_2") (pintype "passive"))
    )
    (net (code "58") (name "Net-(Q25-E)") (class "Default")
      (node (ref "Q25") (pin "2") (pinfunction "E_2") (pintype "passive"))
      (node (ref "R31") (pin "2") (pinfunction "2_2") (pintype "passive"))
    )
    (net (code "59") (name "Net-(Q27-B)") (class "Default")
      (node (ref "D3") (pin "C") (pinfunction "C_C") (pintype "passive"))
      (node (ref "Q27") (pin "1") (pinfunction "B_1") (pintype "passive"))
      (node (ref "R14") (pin "2") (pinfunction "2_2") (pintype "passive"))
    )
    (net (code "60") (name "Net-(Q27-E)") (class "Default")
      (node (ref "Q10") (pin "C") (pinfunction "C_C") (pintype "passive"))
      (node (ref "Q27") (pin "3") (pinfunction "E_3") (pintype "passive"))
    )
    (net (code "61") (name "Net-(Q28-B)") (class "Default")
      (node (ref "D4") (pin "A") (pinfunction "A_A") (pintype "passive"))
      (node (ref "Q28") (pin "1") (pinfunction "B_1") (pintype "passive"))
      (node (ref "R14") (pin "1") (pinfunction "1_1") (pintype "passive"))
    )
    (net (code "62") (name "Net-(Q28-E)") (class "Default")
      (node (ref "Q28") (pin "3") (pinfunction "E_3") (pintype "passive"))
      (node (ref "Q7") (pin "3") (pinfunction "C_3") (pintype "passive"))
    )
    (net (code "63") (name "Net-(Q55-B)") (class "Default")
      (node (ref "D17") (pin "A") (pinfunction "A_A") (pintype "passive"))
      (node (ref "Q55") (pin "1") (pinfunction "B_1") (pintype "passive"))
      (node (ref "Q80") (pin "C") (pinfunction "C_C") (pintype "passive"))
    )
    (net (code "64") (name "Net-(Q55-C)") (class "Default")
      (node (ref "Q55") (pin "3") (pinfunction "C_3") (pintype "passive"))
      (node (ref "Q63") (pin "B") (pinfunction "B_B") (pintype "passive"))
      (node (ref "Q65") (pin "C") (pinfunction "C_C") (pintype "passive"))
    )
    (net (code "65") (name "Net-(Q55-E)") (class "Default")
      (node (ref "Q55") (pin "2") (pinfunction "E_2") (pintype "passive"))
      (node (ref "Q56") (pin "3") (pinfunction "C_3") (pintype "passive"))
    )
    (net (code "66") (name "Net-(Q56-B)") (class "Default")
      (node (ref "D17") (pin "C") (pinfunction "C_C") (pintype "passive"))
      (node (ref "Q56") (pin "1") (pinfunction "B_1") (pintype "passive"))
      (node (ref "R69") (pin "2") (pinfunction "2_2") (pintype "passive"))
    )
    (net (code "67") (name "Net-(Q56-E)") (class "Default")
      (node (ref "Q56") (pin "2") (pinfunction "E_2") (pintype "passive"))
      (node (ref "Q64") (pin "3") (pinfunction "C_3") (pintype "passive"))
      (node (ref "R64") (pin "2") (pinfunction "2_2") (pintype "passive"))
    )
    (net (code "68") (name "Net-(Q57-PadC)") (class "Default")
      (node (ref "Q57") (pin "C") (pinfunction "C_C") (pintype "passive"))
      (node (ref "Q58") (pin "E") (pinfunction "E_E") (pintype "passive"))
    )
    (net (code "69") (name "Net-(Q57-PadE)") (class "Default")
      (node (ref "Q57") (pin "E") (pinfunction "E_E") (pintype "passive"))
      (node (ref "Q62") (pin "C") (pinfunction "C_C") (pintype "passive"))
      (node (ref "R65") (pin "1") (pinfunction "1_1") (pintype "passive"))
    )
    (net (code "70") (name "Net-(Q59-B)") (class "Default")
      (node (ref "C17") (pin "1") (pinfunction "1_1") (pintype "passive"))
      (node (ref "C19") (pin "2") (pinfunction "2_2") (pintype "passive"))
      (node (ref "Q59") (pin "1") (pinfunction "B_1") (pintype "passive"))
      (node (ref "Q67") (pin "2") (pinfunction "C_2") (pintype "passive"))
      (node (ref "Q67") (pin "4") (pinfunction "C_4") (pintype "passive"))
      (node (ref "Q74") (pin "4") (pinfunction "C_4") (pintype "passive"))
      (node (ref "Q75") (pin "C") (pinfunction "C_C") (pintype "passive"))
      (node (ref "R76") (pin "1") (pinfunction "1_1") (pintype "passive"))
      (node (ref "R90") (pin "2") (pinfunction "2_2") (pintype "passive"))
    )
    (net (code "71") (name "Net-(Q59-E)") (class "Default")
      (node (ref "Q59") (pin "3") (pinfunction "E_3") (pintype "passive"))
      (node (ref "Q68") (pin "1") (pinfunction "B_1") (pintype "passive"))
      (node (ref "R79") (pin "2") (pinfunction "2_2") (pintype "passive"))
    )
    (net (code "72") (name "Net-(Q60-B)") (class "Default")
      (node (ref "C17") (pin "2") (pinfunction "2_2") (pintype "passive"))
      (node (ref "C20") (pin "1") (pinfunction "1_1") (pintype "passive"))
      (node (ref "Q60") (pin "1") (pinfunction "B_1") (pintype "passive"))
      (node (ref "Q74") (pin "1") (pinfunction "B_1") (pintype "passive"))
      (node (ref "Q77") (pin "3") (pinfunction "C_3") (pintype "passive"))
      (node (ref "Q79") (pin "2") (pinfunction "C_2") (pintype "passive"))
      (node (ref "Q79") (pin "4") (pinfunction "C_4") (pintype "passive"))
      (node (ref "R78") (pin "2") (pinfunction "2_2") (pintype "passive"))
      (node (ref "R90") (pin "1") (pinfunction "1_1") (pintype "passive"))
      (node (ref "RV3") (pin "1") (pinfunction "A_1") (pintype "passive"))
      (node (ref "RV3") (pin "2") (pinfunction "S_2") (pintype "passive"))
    )
    (net (code "73") (name "Net-(Q60-E)") (class "Default")
      (node (ref "Q60") (pin "3") (pinfunction "E_3") (pintype "passive"))
      (node (ref "Q69") (pin "1") (pinfunction "B_1") (pintype "passive"))
      (node (ref "R79") (pin "1") (pinfunction "1_1") (pintype "passive"))
    )
    (net (code "74") (name "Net-(Q61-B)") (class "Default")
      (node (ref "Q58") (pin "C") (pinfunction "C_C") (pintype "passive"))
      (node (ref "Q61") (pin "1") (pinfunction "B_1") (pintype "passive"))
      (node (ref "Q72") (pin "3") (pinfunction "C_3") (pintype "passive"))
    )
    (net (code "75") (name "Net-(Q61-C)") (class "Default")
      (node (ref "Q61") (pin "3") (pinfunction "C_3") (pintype "passive"))
      (node (ref "Q79") (pin "3") (pinfunction "E_3") (pintype "passive"))
    )
    (net (code "76") (name "Net-(Q61-E)") (class "Default")
      (node (ref "Q61") (pin "2") (pinfunction "E_2") (pintype "passive"))
      (node (ref "Q72") (pin "1") (pinfunction "B_1") (pintype "passive"))
      (node (ref "Q73") (pin "1") (pinfunction "B_1") (pintype "passive"))
      (node (ref "Q73") (pin "3") (pinfunction "C_3") (pintype "passive"))
    )
    (net (code "77") (name "Net-(Q62-PadE)") (class "Default")
      (node (ref "Q62") (pin "E") (pinfunction "E_E") (pintype "passive"))
      (node (ref "R69") (pin "1") (pinfunction "1_1") (pintype "passive"))
    )
    (net (code "78") (name "Net-(Q63-PadE)") (class "Default")
      (node (ref "Q63") (pin "E") (pinfunction "E_E") (pintype "passive"))
      (node (ref "Q65") (pin "B") (pinfunction "B_B") (pintype "passive"))
      (node (ref "Q66") (pin "B") (pinfunction "B_B") (pintype "passive"))
      (node (ref "Q66") (pin "C") (pinfunction "C_C") (pintype "passive"))
    )
    (net (code "79") (name "Net-(Q64-B)") (class "Default")
      (node (ref "Q62") (pin "B") (pinfunction "B_B") (pintype "passive"))
      (node (ref "Q64") (pin "1") (pinfunction "B_1") (pintype "passive"))
      (node (ref "R80") (pin "2") (pinfunction "2_2") (pintype "passive"))
      (node (ref "R91") (pin "1") (pinfunction "1_1") (pintype "passive"))
    )
    (net (code "80") (name "Net-(Q64-E)") (class "Default")
      (node (ref "Q64") (pin "2") (pinfunction "E_2") (pintype "passive"))
      (node (ref "R70") (pin "2") (pinfunction "2_2") (pintype "passive"))
    )
    (net (code "81") (name "Net-(Q65-PadE)") (class "Default")
      (node (ref "Q65") (pin "E") (pinfunction "E_E") (pintype "passive"))
      (node (ref "R72") (pin "1") (pinfunction "1_1") (pintype "passive"))
    )
    (net (code "82") (name "Net-(Q67-B)") (class "Default")
      (node (ref "D19") (pin "C") (pinfunction "C_C") (pintype "passive"))
      (node (ref "Q67") (pin "1") (pinfunction "B_1") (pintype "passive"))
      (node (ref "R77") (pin "2") (pinfunction "2_2") (pintype "passive"))
    )
    (net (code "83") (name "Net-(Q67-E)") (class "Default")
      (node (ref "Q63") (pin "C") (pinfunction "C_C") (pintype "passive"))
      (node (ref "Q67") (pin "3") (pinfunction "E_3") (pintype "passive"))
    )
    (net (code "84") (name "Net-(Q68-E)") (class "Default")
      (node (ref "Q68") (pin "3") (pinfunction "E_3") (pintype "passive"))
      (node (ref "Q70") (pin "1") (pinfunction "B_1") (pintype "passive"))
      (node (ref "R71") (pin "2") (pinfunction "2_2") (pintype "passive"))
    )
    (net (code "85") (name "Net-(Q69-E)") (class "Default")
      (node (ref "Q69") (pin "3") (pinfunction "E_3") (pintype "passive"))
      (node (ref "Q71") (pin "1") (pinfunction "B_1") (pintype "passive"))
      (node (ref "R71") (pin "1") (pinfunction "1_1") (pintype "passive"))
    )
    (net (code "86") (name "Net-(Q70-E)") (class "Default")
      (node (ref "Q70") (pin "3") (pinfunction "E_3") (pintype "passive"))
      (node (ref "R87") (pin "2") (pinfunction "2_2") (pintype "passive"))
    )
    (net (code "87") (name "Net-(Q71-E)") (class "Default")
      (node (ref "Q71") (pin "3") (pinfunction "E_3") (pintype "passive"))
      (node (ref "R88") (pin "1") (pinfunction "1_1") (pintype "passive"))
    )
    (net (code "88") (name "Net-(Q72-E)") (class "Default")
      (node (ref "Q72") (pin "2") (pinfunction "E_2") (pintype "passive"))
      (node (ref "R74") (pin "2") (pinfunction "2_2") (pintype "passive"))
    )
    (net (code "89") (name "Net-(Q73-E)") (class "Default")
      (node (ref "D20") (pin "C") (pinfunction "C_C") (pintype "passive"))
      (node (ref "Q73") (pin "2") (pinfunction "E_2") (pintype "passive"))
      (node (ref "R75") (pin "2") (pinfunction "2_2") (pintype "passive"))
    )
    (net (code "90") (name "Net-(Q74-E)") (class "Default")
      (node (ref "Q74") (pin "3") (pinfunction "E_3") (pintype "passive"))
      (node (ref "RV3") (pin "3") (pinfunction "E_3") (pintype "passive"))
    )
    (net (code "91") (name "Net-(Q75-PadB)") (class "Default")
      (node (ref "Q75") (pin "B") (pinfunction "B_B") (pintype "passive"))
      (node (ref "Q76") (pin "B") (pinfunction "B_B") (pintype "passive"))
      (node (ref "Q76") (pin "C") (pinfunction "C_C") (pintype "passive"))
      (node (ref "R82") (pin "2") (pinfunction "2_2") (pintype "passive"))
    )
    (net (code "92") (name "Net-(Q75-PadE)") (class "Default")
      (node (ref "Q75") (pin "E") (pinfunction "E_E") (pintype "passive"))
      (node (ref "R84") (pin "1") (pinfunction "1_1") (pintype "passive"))
    )
    (net (code "93") (name "Net-(Q76-PadE)") (class "Default")
      (node (ref "Q76") (pin "E") (pinfunction "E_E") (pintype "passive"))
      (node (ref "R85") (pin "1") (pinfunction "1_1") (pintype "passive"))
    )
    (net (code "94") (name "Net-(Q77-B)") (class "Default")
      (node (ref "Q77") (pin "1") (pinfunction "B_1") (pintype "passive"))
      (node (ref "Q78") (pin "1") (pinfunction "B_1") (pintype "passive"))
      (node (ref "Q78") (pin "3") (pinfunction "C_3") (pintype "passive"))
      (node (ref "R83") (pin "1") (pinfunction "1_1") (pintype "passive"))
    )
    (net (code "95") (name "Net-(Q77-E)") (class "Default")
      (node (ref "Q77") (pin "2") (pinfunction "E_2") (pintype "passive"))
      (node (ref "R86") (pin "2") (pinfunction "2_2") (pintype "passive"))
    )
    (net (code "96") (name "Net-(Q78-E)") (class "Default")
      (node (ref "Q78") (pin "2") (pinfunction "E_2") (pintype "passive"))
      (node (ref "R89") (pin "2") (pinfunction "2_2") (pintype "passive"))
    )
    (net (code "97") (name "Net-(Q79-B)") (class "Default")
      (node (ref "D20") (pin "A") (pinfunction "A_A") (pintype "passive"))
      (node (ref "Q79") (pin "1") (pinfunction "B_1") (pintype "passive"))
      (node (ref "R77") (pin "1") (pinfunction "1_1") (pintype "passive"))
    )
    (net (code "98") (name "Net-(Q80-PadE)") (class "Default")
      (node (ref "Q80") (pin "E") (pinfunction "E_E") (pintype "passive"))
      (node (ref "R63") (pin "1") (pinfunction "1_1") (pintype "passive"))
    )
    (net (code "99") (name "Net-(Q81-B)") (class "Default")
      (node (ref "D23") (pin "A") (pinfunction "A_A") (pintype "passive"))
      (node (ref "Q81") (pin "1") (pinfunction "B_1") (pintype "passive"))
      (node (ref "R67") (pin "1") (pinfunction "1_1") (pintype "passive"))
    )
    (net (code "100") (name "Net-(Q81-C)") (class "Default")
      (node (ref "D22") (pin "C") (pinfunction "C_C") (pintype "passive"))
      (node (ref "Q58") (pin "B") (pinfunction "B_B") (pintype "passive"))
      (node (ref "Q81") (pin "3") (pinfunction "C_3") (pintype "passive"))
    )
    (net (code "101") (name "Net-(Q81-E)") (class "Default")
      (node (ref "Q81") (pin "2") (pinfunction "E_2") (pintype "passive"))
      (node (ref "R66") (pin "2") (pinfunction "2_2") (pintype "passive"))
    )
    (net (code "102") (name "Net-(R1-Pad1)") (class "Default")
      (node (ref "R1") (pin "1") (pinfunction "1_1") (pintype "passive"))
      (node (ref "R2") (pin "2") (pinfunction "2_2") (pintype "passive"))
      (node (ref "R4") (pin "1") (pinfunction "1_1") (pintype "passive"))
      (node (ref "R5") (pin "2") (pinfunction "2_2") (pintype "passive"))
    )
    (net (code "103") (name "Net-(R1-Pad2)") (class "Default")
      (node (ref "R1") (pin "2") (pinfunction "2_2") (pintype "passive"))
      (node (ref "R27") (pin "1") (pinfunction "1_1") (pintype "passive"))
      (node (ref "R28") (pin "2") (pinfunction "2_2") (pintype "passive"))
      (node (ref "R8") (pin "1") (pinfunction "1_1") (pintype "passive"))
    )
    (net (code "104") (name "Net-(R61-Pad1)") (class "Default")
      (node (ref "R61") (pin "1") (pinfunction "1_1") (pintype "passive"))
      (node (ref "R62") (pin "2") (pinfunction "2_2") (pintype "passive"))
      (node (ref "R64") (pin "1") (pinfunction "1_1") (pintype "passive"))
      (node (ref "R65") (pin "2") (pinfunction "2_2") (pintype "passive"))
    )
    (net (code "105") (name "Net-(R61-Pad2)") (class "Default")
      (node (ref "R61") (pin "2") (pinfunction "2_2") (pintype "passive"))
      (node (ref "R68") (pin "1") (pinfunction "1_1") (pintype "passive"))
      (node (ref "R87") (pin "1") (pinfunction "1_1") (pintype "passive"))
      (node (ref "R88") (pin "2") (pinfunction "2_2") (pintype "passive"))
    )
    (net (code "106") (name "unconnected-(R20-Pad2)") (class "Default")
      (node (ref "R20") (pin "2") (pinfunction "2_2") (pintype "passive"))
    )
    (net (code "107") (name "unconnected-(R91-Pad2)") (class "Default")
      (node (ref "R91") (pin "2") (pinfunction "2_2") (pintype "passive"))
    )
  )
)
